# STM32.net
KiCad netlist of a schematic drawn in Altium Designer
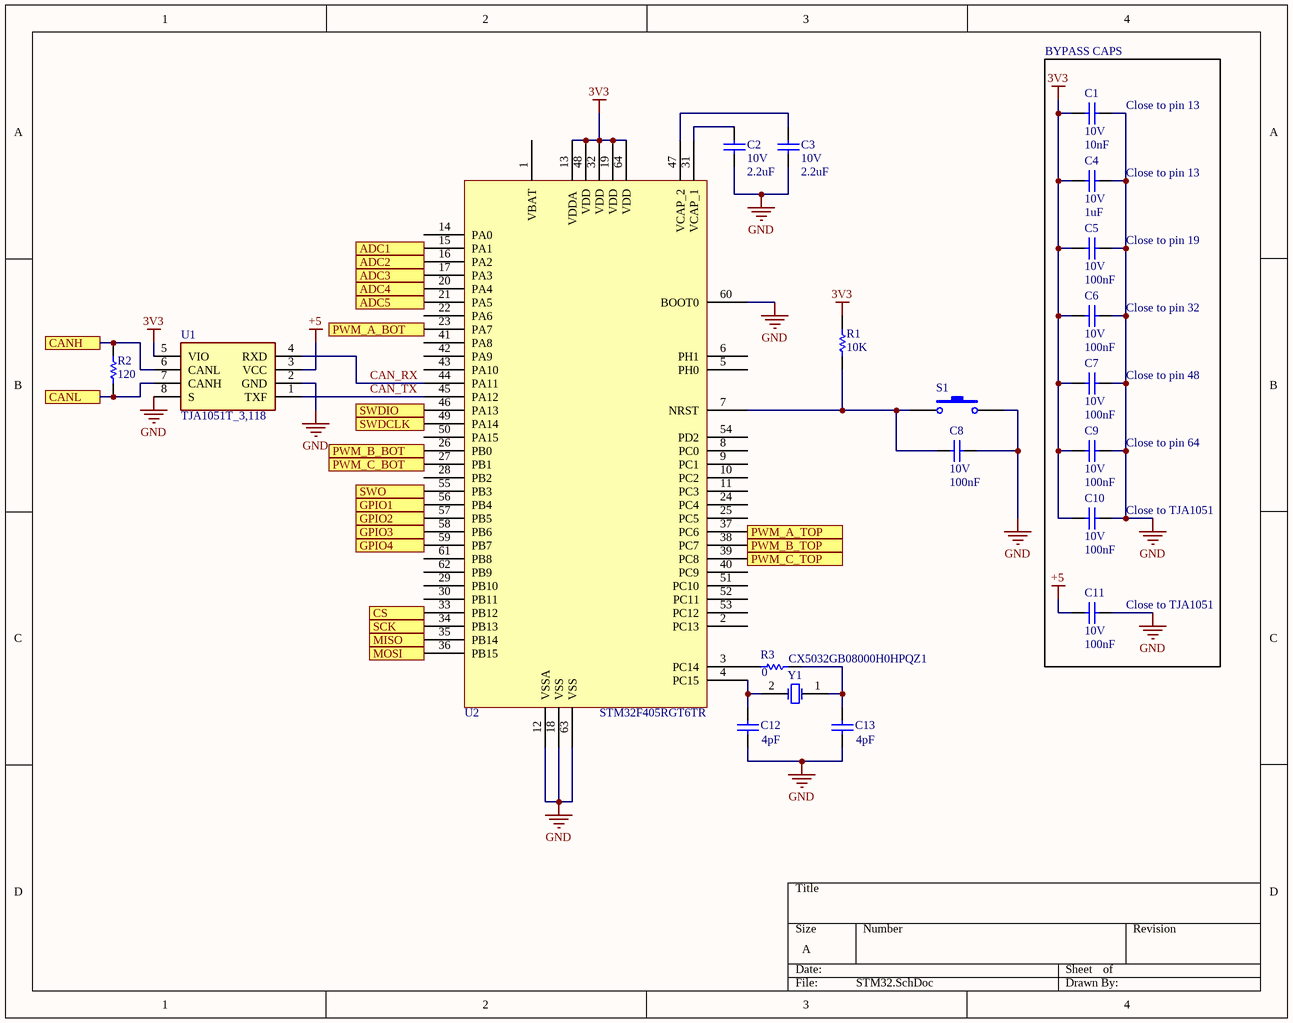
[diagram p0: STM32.SchDoc]

(export (version "E")
  (design (tool "Eeschema 10.0.6"))
  (components
    (comp (ref "C1")
      (value "10V")
      (footprint "C0805")
      (description "C0805C103K8RAC7800. 10000pF ±10% 10V Ceramic Capacitor X7R 0805 (2012 Metric)")
      (fields (field (name "ALTIUM_VALUE") "10nF") (field (name "PUBLISHER") "Altium Limited"))
      (libsource (lib "Miscellaneous Devices") (part "Cap"))
    )
    (comp (ref "C2")
      (value "10V")
      (footprint "C0805")
      (description "C0805C225K8RACAUTO. 2.2µF ±10% 10V Ceramic Capacitor X7R 0805 (2012 Metric)")
      (fields (field (name "ALTIUM_VALUE") "2.2uF") (field (name "PUBLISHER") "Altium Limited"))
      (libsource (lib "Miscellaneous Devices") (part "Cap"))
    )
    (comp (ref "C3")
      (value "10V")
      (footprint "C0805")
      (description "C0805C225K8RACAUTO. 2.2µF ±10% 10V Ceramic Capacitor X7R 0805 (2012 Metric)")
      (fields (field (name "ALTIUM_VALUE") "2.2uF") (field (name "PUBLISHER") "Altium Limited"))
      (libsource (lib "Miscellaneous Devices") (part "Cap"))
    )
    (comp (ref "C4")
      (value "10V")
      (footprint "C0805")
      (description "CL21B105KPFNNNE. 1µF ±10% 10V Ceramic Capacitor X7R 0805 (2012 Metric)")
      (fields (field (name "ALTIUM_VALUE") "1uF") (field (name "PUBLISHER") "Altium Limited"))
      (libsource (lib "Miscellaneous Devices") (part "Cap"))
    )
    (comp (ref "C5")
      (value "10V")
      (footprint "C0805")
      (description "C0805C104K8RACTU. 0.1µF ±10% 10V Ceramic Capacitor X7R 0805 (2012 Metric)")
      (fields (field (name "ALTIUM_VALUE") "100nF") (field (name "PUBLISHER") "Altium Limited"))
      (libsource (lib "Miscellaneous Devices") (part "Cap"))
    )
    (comp (ref "C6")
      (value "10V")
      (footprint "C0805")
      (description "C0805C104K8RACTU. 0.1µF ±10% 10V Ceramic Capacitor X7R 0805 (2012 Metric)")
      (fields (field (name "ALTIUM_VALUE") "100nF") (field (name "PUBLISHER") "Altium Limited"))
      (libsource (lib "Miscellaneous Devices") (part "Cap"))
    )
    (comp (ref "C7")
      (value "10V")
      (footprint "C0805")
      (description "C0805C104K8RACTU. 0.1µF ±10% 10V Ceramic Capacitor X7R 0805 (2012 Metric)")
      (fields (field (name "ALTIUM_VALUE") "100nF") (field (name "PUBLISHER") "Altium Limited"))
      (libsource (lib "Miscellaneous Devices") (part "Cap"))
    )
    (comp (ref "C8")
      (value "10V")
      (footprint "C0805")
      (description "C0805C104K8RACTU. 0.1µF ±10% 10V Ceramic Capacitor X7R 0805 (2012 Metric)")
      (fields (field (name "ALTIUM_VALUE") "100nF") (field (name "PUBLISHER") "Altium Limited"))
      (libsource (lib "Miscellaneous Devices") (part "Cap"))
    )
    (comp (ref "C9")
      (value "10V")
      (footprint "C0805")
      (description "C0805C104K8RACTU. 0.1µF ±10% 10V Ceramic Capacitor X7R 0805 (2012 Metric)")
      (fields (field (name "ALTIUM_VALUE") "100nF") (field (name "PUBLISHER") "Altium Limited"))
      (libsource (lib "Miscellaneous Devices") (part "Cap"))
    )
    (comp (ref "C10")
      (value "10V")
      (footprint "C0805")
      (description "C0805C104K8RACTU. 0.1µF ±10% 10V Ceramic Capacitor X7R 0805 (2012 Metric)")
      (fields (field (name "ALTIUM_VALUE") "100nF") (field (name "PUBLISHER") "Altium Limited"))
      (libsource (lib "Miscellaneous Devices") (part "Cap"))
    )
    (comp (ref "C11")
      (value "10V")
      (footprint "C0805")
      (description "C0805C104K8RACTU. 0.1µF ±10% 10V Ceramic Capacitor X7R 0805 (2012 Metric)")
      (fields (field (name "ALTIUM_VALUE") "100nF") (field (name "PUBLISHER") "Altium Limited"))
      (libsource (lib "Miscellaneous Devices") (part "Cap"))
    )
    (comp (ref "C12")
      (value "4pF")
      (footprint "C0805")
      (description "CBR08C409B5GAC. 4pF ±0.1pF 50V Ceramic Capacitor C0G, NP0 0805 (2012 Metric)")
      (fields (field (name "Comment") "50V") (field (name "PUBLISHER") "Altium Limited"))
      (libsource (lib "Miscellaneous Devices") (part "Cap"))
    )
    (comp (ref "C13")
      (value "4pF")
      (footprint "C0805")
      (description "CBR08C409B5GAC")
      (fields (field (name "Comment") "50V") (field (name "PUBLISHER") "Altium Limited"))
      (libsource (lib "Miscellaneous Devices") (part "Cap"))
    )
    (comp (ref "R1")
      (value "10K")
      (footprint "J1-0603")
      (fields (field (name "Comment") "5%") (field (name "PUBLISHER") "Altium Limited"))
      (libsource (lib "Miscellaneous Devices") (part "Res1"))
    )
    (comp (ref "R2")
      (value "120")
      (footprint "J1-0603")
      (fields (field (name "Comment") "5%") (field (name "PUBLISHER") "Altium Limited"))
      (libsource (lib "Miscellaneous Devices") (part "Res1"))
    )
    (comp (ref "R3")
      (value "0")
      (footprint "J1-0603")
      (fields (field (name "Comment") "0603") (field (name "PUBLISHER") "Altium Limited"))
      (libsource (lib "Miscellaneous Devices") (part "Res1"))
    )
    (comp (ref "S1")
      (value "SW-PB")
      (footprint "PTS636 SM43 SMTR LFS")
      (description "Switch")
      (fields (field (name "PUBLISHER") "Altium Limited"))
      (libsource (lib "Miscellaneous Devices") (part "SW-PB"))
    )
    (comp (ref "U1")
      (value "TJA1051T_3,118")
      (footprint "Motor Controller:SOIC127P600X175-8N")
      (description "Integrated Circuit")
      (fields
        (field (name "MANUFACTURER_PART_NUMBER") "TJA1051T/3,118")
        (field (name "MOUSER PART NUMBER") "771-TJA1051T3118")
      )
      (libsource (lib "Motor Controller") (part "TJA1051T_3,118"))
    )
    (comp (ref "U2")
      (value "STM32F405RGT6TR")
      (footprint "STM32F405RGT6TR")
      (libsource (lib "Motor Controller") (part "STM32F405RGT6TR"))
    )
    (comp (ref "Y1")
      (value "CX5032GB08000H0HPQZ1")
      (footprint "CX5032GB08000H0HPQZ1")
      (description "8MHz ±20ppm Crystal 12pF 300 Ohms 2-SMD, No Lead")
      (fields (field (name "PUBLISHER") "Altium Limited"))
      (libsource (lib "Miscellaneous Devices") (part "XTAL"))
    )
  )
  (nets
    (net (code "1") (name "+5") (class "Default")
      (node (ref "C11") (pin "1") (pinfunction "1_1") (pintype "passive"))
      (node (ref "U1") (pin "3") (pinfunction "VCC_3") (pintype "passive"))
    )
    (net (code "2") (name "/ADC1") (class "Default")
      (node (ref "U2") (pin "15") (pinfunction "PA1_15") (pintype "passive"))
    )
    (net (code "3") (name "/ADC2") (class "Default")
      (node (ref "U2") (pin "16") (pinfunction "PA2_16") (pintype "passive"))
    )
    (net (code "4") (name "/ADC3") (class "Default")
      (node (ref "U2") (pin "17") (pinfunction "PA3_17") (pintype "passive"))
    )
    (net (code "5") (name "/ADC4") (class "Default")
      (node (ref "U2") (pin "20") (pinfunction "PA4_20") (pintype "passive"))
    )
    (net (code "6") (name "/ADC5") (class "Default")
      (node (ref "U2") (pin "21") (pinfunction "PA5_21") (pintype "passive"))
    )
    (net (code "7") (name "/CANH") (class "Default")
      (node (ref "R2") (pin "2") (pinfunction "2_2") (pintype "passive"))
      (node (ref "U1") (pin "6") (pinfunction "CANL_6") (pintype "passive"))
    )
    (net (code "8") (name "/CANL") (class "Default")
      (node (ref "R2") (pin "1") (pinfunction "1_1") (pintype "passive"))
      (node (ref "U1") (pin "7") (pinfunction "CANH_7") (pintype "passive"))
    )
    (net (code "9") (name "/CAN_RX") (class "Default")
      (node (ref "U1") (pin "4") (pinfunction "RXD_4") (pintype "passive"))
      (node (ref "U2") (pin "44") (pinfunction "PA11_44") (pintype "passive"))
    )
    (net (code "10") (name "/CAN_TX") (class "Default")
      (node (ref "U1") (pin "1") (pinfunction "TXF_1") (pintype "passive"))
      (node (ref "U2") (pin "45") (pinfunction "PA12_45") (pintype "passive"))
    )
    (net (code "11") (name "/CS") (class "Default")
      (node (ref "U2") (pin "33") (pinfunction "PB12_33") (pintype "passive"))
    )
    (net (code "12") (name "/GPIO1") (class "Default")
      (node (ref "U2") (pin "56") (pinfunction "PB4_56") (pintype "passive"))
    )
    (net (code "13") (name "/GPIO2") (class "Default")
      (node (ref "U2") (pin "57") (pinfunction "PB5_57") (pintype "passive"))
    )
    (net (code "14") (name "/GPIO3") (class "Default")
      (node (ref "U2") (pin "58") (pinfunction "PB6_58") (pintype "passive"))
    )
    (net (code "15") (name "/GPIO4") (class "Default")
      (node (ref "U2") (pin "59") (pinfunction "PB7_59") (pintype "passive"))
    )
    (net (code "16") (name "/MISO") (class "Default")
      (node (ref "U2") (pin "35") (pinfunction "PB14_35") (pintype "passive"))
    )
    (net (code "17") (name "/MOSI") (class "Default")
      (node (ref "U2") (pin "36") (pinfunction "PB15_36") (pintype "passive"))
    )
    (net (code "18") (name "/PWM_A_BOT") (class "Default")
      (node (ref "U2") (pin "23") (pinfunction "PA7_23") (pintype "passive"))
    )
    (net (code "19") (name "/PWM_A_TOP") (class "Default")
      (node (ref "U2") (pin "37") (pinfunction "PC6_37") (pintype "passive"))
    )
    (net (code "20") (name "/PWM_B_BOT") (class "Default")
      (node (ref "U2") (pin "26") (pinfunction "PB0_26") (pintype "passive"))
    )
    (net (code "21") (name "/PWM_B_TOP") (class "Default")
      (node (ref "U2") (pin "38") (pinfunction "PC7_38") (pintype "passive"))
    )
    (net (code "22") (name "/PWM_C_BOT") (class "Default")
      (node (ref "U2") (pin "27") (pinfunction "PB1_27") (pintype "passive"))
    )
    (net (code "23") (name "/PWM_C_TOP") (class "Default")
      (node (ref "U2") (pin "39") (pinfunction "PC8_39") (pintype "passive"))
    )
    (net (code "24") (name "/SCK") (class "Default")
      (node (ref "U2") (pin "34") (pinfunction "PB13_34") (pintype "passive"))
    )
    (net (code "25") (name "/SWDCLK") (class "Default")
      (node (ref "U2") (pin "49") (pinfunction "PA14_49") (pintype "passive"))
    )
    (net (code "26") (name "/SWDIO") (class "Default")
      (node (ref "U2") (pin "46") (pinfunction "PA13_46") (pintype "passive"))
    )
    (net (code "27") (name "/SWO") (class "Default")
      (node (ref "U2") (pin "55") (pinfunction "PB3_55") (pintype "passive"))
    )
    (net (code "28") (name "3V3") (class "Default")
      (node (ref "C1") (pin "1") (pinfunction "1_1") (pintype "passive"))
      (node (ref "C10") (pin "1") (pinfunction "1_1") (pintype "passive"))
      (node (ref "C4") (pin "2") (pinfunction "2_2") (pintype "passive"))
      (node (ref "C5") (pin "1") (pinfunction "1_1") (pintype "passive"))
      (node (ref "C6") (pin "1") (pinfunction "1_1") (pintype "passive"))
      (node (ref "C7") (pin "1") (pinfunction "1_1") (pintype "passive"))
      (node (ref "C9") (pin "1") (pinfunction "1_1") (pintype "passive"))
      (node (ref "R1") (pin "2") (pinfunction "2_2") (pintype "passive"))
      (node (ref "U1") (pin "5") (pinfunction "VIO_5") (pintype "passive"))
      (node (ref "U2") (pin "13") (pinfunction "VDDA_13") (pintype "power_in"))
      (node (ref "U2") (pin "19") (pinfunction "VDD_19") (pintype "power_in"))
      (node (ref "U2") (pin "32") (pinfunction "VDD_32") (pintype "power_in"))
      (node (ref "U2") (pin "48") (pinfunction "VDD_48") (pintype "power_in"))
      (node (ref "U2") (pin "64") (pinfunction "VDD_64") (pintype "power_in"))
    )
    (net (code "29") (name "GND") (class "Default")
      (node (ref "C1") (pin "2") (pinfunction "2_2") (pintype "passive"))
      (node (ref "C10") (pin "2") (pinfunction "2_2") (pintype "passive"))
      (node (ref "C11") (pin "2") (pinfunction "2_2") (pintype "passive"))
      (node (ref "C12") (pin "1") (pinfunction "1_1") (pintype "passive"))
      (node (ref "C13") (pin "1") (pinfunction "1_1") (pintype "passive"))
      (node (ref "C2") (pin "1") (pinfunction "1_1") (pintype "passive"))
      (node (ref "C3") (pin "1") (pinfunction "1_1") (pintype "passive"))
      (node (ref "C4") (pin "1") (pinfunction "1_1") (pintype "passive"))
      (node (ref "C5") (pin "2") (pinfunction "2_2") (pintype "passive"))
      (node (ref "C6") (pin "2") (pinfunction "2_2") (pintype "passive"))
      (node (ref "C7") (pin "2") (pinfunction "2_2") (pintype "passive"))
      (node (ref "C8") (pin "2") (pinfunction "2_2") (pintype "passive"))
      (node (ref "C9") (pin "2") (pinfunction "2_2") (pintype "passive"))
      (node (ref "S1") (pin "2") (pinfunction "2_2") (pintype "passive"))
      (node (ref "U1") (pin "2") (pinfunction "GND_2") (pintype "passive"))
      (node (ref "U1") (pin "8") (pinfunction "S_8") (pintype "passive"))
      (node (ref "U2") (pin "12") (pinfunction "VSSA_12") (pintype "power_in"))
      (node (ref "U2") (pin "18") (pinfunction "VSS_18") (pintype "power_in"))
      (node (ref "U2") (pin "60") (pinfunction "BOOT0_60") (pintype "passive"))
      (node (ref "U2") (pin "63") (pinfunction "VSS_63") (pintype "power_in"))
    )
    (net (code "30") (name "Net-(U2-NRST)") (class "Default")
      (node (ref "C8") (pin "1") (pinfunction "1_1") (pintype "passive"))
      (node (ref "R1") (pin "1") (pinfunction "1_1") (pintype "passive"))
      (node (ref "S1") (pin "1") (pinfunction "1_1") (pintype "passive"))
      (node (ref "U2") (pin "7") (pinfunction "NRST_7") (pintype "passive"))
    )
    (net (code "31") (name "Net-(U2-PC14)") (class "Default")
      (node (ref "R3") (pin "1") (pinfunction "1_1") (pintype "passive"))
      (node (ref "U2") (pin "3") (pinfunction "PC14_3") (pintype "passive"))
    )
    (net (code "32") (name "Net-(U2-PC15)") (class "Default")
      (node (ref "C12") (pin "2") (pinfunction "2_2") (pintype "passive"))
      (node (ref "U2") (pin "4") (pinfunction "PC15_4") (pintype "passive"))
      (node (ref "Y1") (pin "2") (pinfunction "OSC2_2") (pintype "passive"))
    )
    (net (code "33") (name "Net-(U2-VCAP_1)") (class "Default")
      (node (ref "C2") (pin "2") (pinfunction "2_2") (pintype "passive"))
      (node (ref "U2") (pin "31") (pinfunction "VCAP_1_31") (pintype "power_in"))
    )
    (net (code "34") (name "Net-(U2-VCAP_2)") (class "Default")
      (node (ref "C3") (pin "2") (pinfunction "2_2") (pintype "passive"))
      (node (ref "U2") (pin "47") (pinfunction "VCAP_2_47") (pintype "power_in"))
    )
    (net (code "35") (name "Net-(Y1-OSC1)") (class "Default")
      (node (ref "C13") (pin "2") (pinfunction "2_2") (pintype "passive"))
      (node (ref "R3") (pin "2") (pinfunction "2_2") (pintype "passive"))
      (node (ref "Y1") (pin "1") (pinfunction "OSC1_1") (pintype "passive"))
    )
    (net (code "36") (name "unconnected-(U2-PA0-Pad14)") (class "Default")
      (node (ref "U2") (pin "14") (pinfunction "PA0_14") (pintype "passive"))
    )
    (net (code "37") (name "unconnected-(U2-PA6-Pad22)") (class "Default")
      (node (ref "U2") (pin "22") (pinfunction "PA6_22") (pintype "passive"))
    )
    (net (code "38") (name "unconnected-(U2-PA8-Pad41)") (class "Default")
      (node (ref "U2") (pin "41") (pinfunction "PA8_41") (pintype "passive"))
    )
    (net (code "39") (name "unconnected-(U2-PA9-Pad42)") (class "Default")
      (node (ref "U2") (pin "42") (pinfunction "PA9_42") (pintype "passive"))
    )
    (net (code "40") (name "unconnected-(U2-PA10-Pad43)") (class "Default")
      (node (ref "U2") (pin "43") (pinfunction "PA10_43") (pintype "passive"))
    )
    (net (code "41") (name "unconnected-(U2-PA15-Pad50)") (class "Default")
      (node (ref "U2") (pin "50") (pinfunction "PA15_50") (pintype "passive"))
    )
    (net (code "42") (name "unconnected-(U2-PB2-Pad28)") (class "Default")
      (node (ref "U2") (pin "28") (pinfunction "PB2_28") (pintype "passive"))
    )
    (net (code "43") (name "unconnected-(U2-PB8-Pad61)") (class "Default")
      (node (ref "U2") (pin "61") (pinfunction "PB8_61") (pintype "passive"))
    )
    (net (code "44") (name "unconnected-(U2-PB9-Pad62)") (class "Default")
      (node (ref "U2") (pin "62") (pinfunction "PB9_62") (pintype "passive"))
    )
    (net (code "45") (name "unconnected-(U2-PB10-Pad29)") (class "Default")
      (node (ref "U2") (pin "29") (pinfunction "PB10_29") (pintype "passive"))
    )
    (net (code "46") (name "unconnected-(U2-PB11-Pad30)") (class "Default")
      (node (ref "U2") (pin "30") (pinfunction "PB11_30") (pintype "passive"))
    )
    (net (code "47") (name "unconnected-(U2-PC0-Pad8)") (class "Default")
      (node (ref "U2") (pin "8") (pinfunction "PC0_8") (pintype "passive"))
    )
    (net (code "48") (name "unconnected-(U2-PC1-Pad9)") (class "Default")
      (node (ref "U2") (pin "9") (pinfunction "PC1_9") (pintype "passive"))
    )
    (net (code "49") (name "unconnected-(U2-PC2-Pad10)") (class "Default")
      (node (ref "U2") (pin "10") (pinfunction "PC2_10") (pintype "passive"))
    )
    (net (code "50") (name "unconnected-(U2-PC3-Pad11)") (class "Default")
      (node (ref "U2") (pin "11") (pinfunction "PC3_11") (pintype "passive"))
    )
    (net (code "51") (name "unconnected-(U2-PC4-Pad24)") (class "Default")
      (node (ref "U2") (pin "24") (pinfunction "PC4_24") (pintype "passive"))
    )
    (net (code "52") (name "unconnected-(U2-PC5-Pad25)") (class "Default")
      (node (ref "U2") (pin "25") (pinfunction "PC5_25") (pintype "passive"))
    )
    (net (code "53") (name "unconnected-(U2-PC9-Pad40)") (class "Default")
      (node (ref "U2") (pin "40") (pinfunction "PC9_40") (pintype "passive"))
    )
    (net (code "54") (name "unconnected-(U2-PC10-Pad51)") (class "Default")
      (node (ref "U2") (pin "51") (pinfunction "PC10_51") (pintype "passive"))
    )
    (net (code "55") (name "unconnected-(U2-PC11-Pad52)") (class "Default")
      (node (ref "U2") (pin "52") (pinfunction "PC11_52") (pintype "passive"))
    )
    (net (code "56") (name "unconnected-(U2-PC12-Pad53)") (class "Default")
      (node (ref "U2") (pin "53") (pinfunction "PC12_53") (pintype "passive"))
    )
    (net (code "57") (name "unconnected-(U2-PC13-Pad2)") (class "Default")
      (node (ref "U2") (pin "2") (pinfunction "PC13_2") (pintype "passive"))
    )
    (net (code "58") (name "unconnected-(U2-PD2-Pad54)") (class "Default")
      (node (ref "U2") (pin "54") (pinfunction "PD2_54") (pintype "passive"))
    )
    (net (code "59") (name "unconnected-(U2-PH0-Pad5)") (class "Default")
      (node (ref "U2") (pin "5") (pinfunction "PH0_5") (pintype "passive"))
    )
    (net (code "60") (name "unconnected-(U2-PH1-Pad6)") (class "Default")
      (node (ref "U2") (pin "6") (pinfunction "PH1_6") (pintype "passive"))
    )
    (net (code "61") (name "unconnected-(U2-VBAT-Pad1)") (class "Default")
      (node (ref "U2") (pin "1") (pinfunction "VBAT_1") (pintype "power_in"))
    )
  )
)
